# MOTOR.net
KiCad netlist of a schematic drawn in Altium Designer
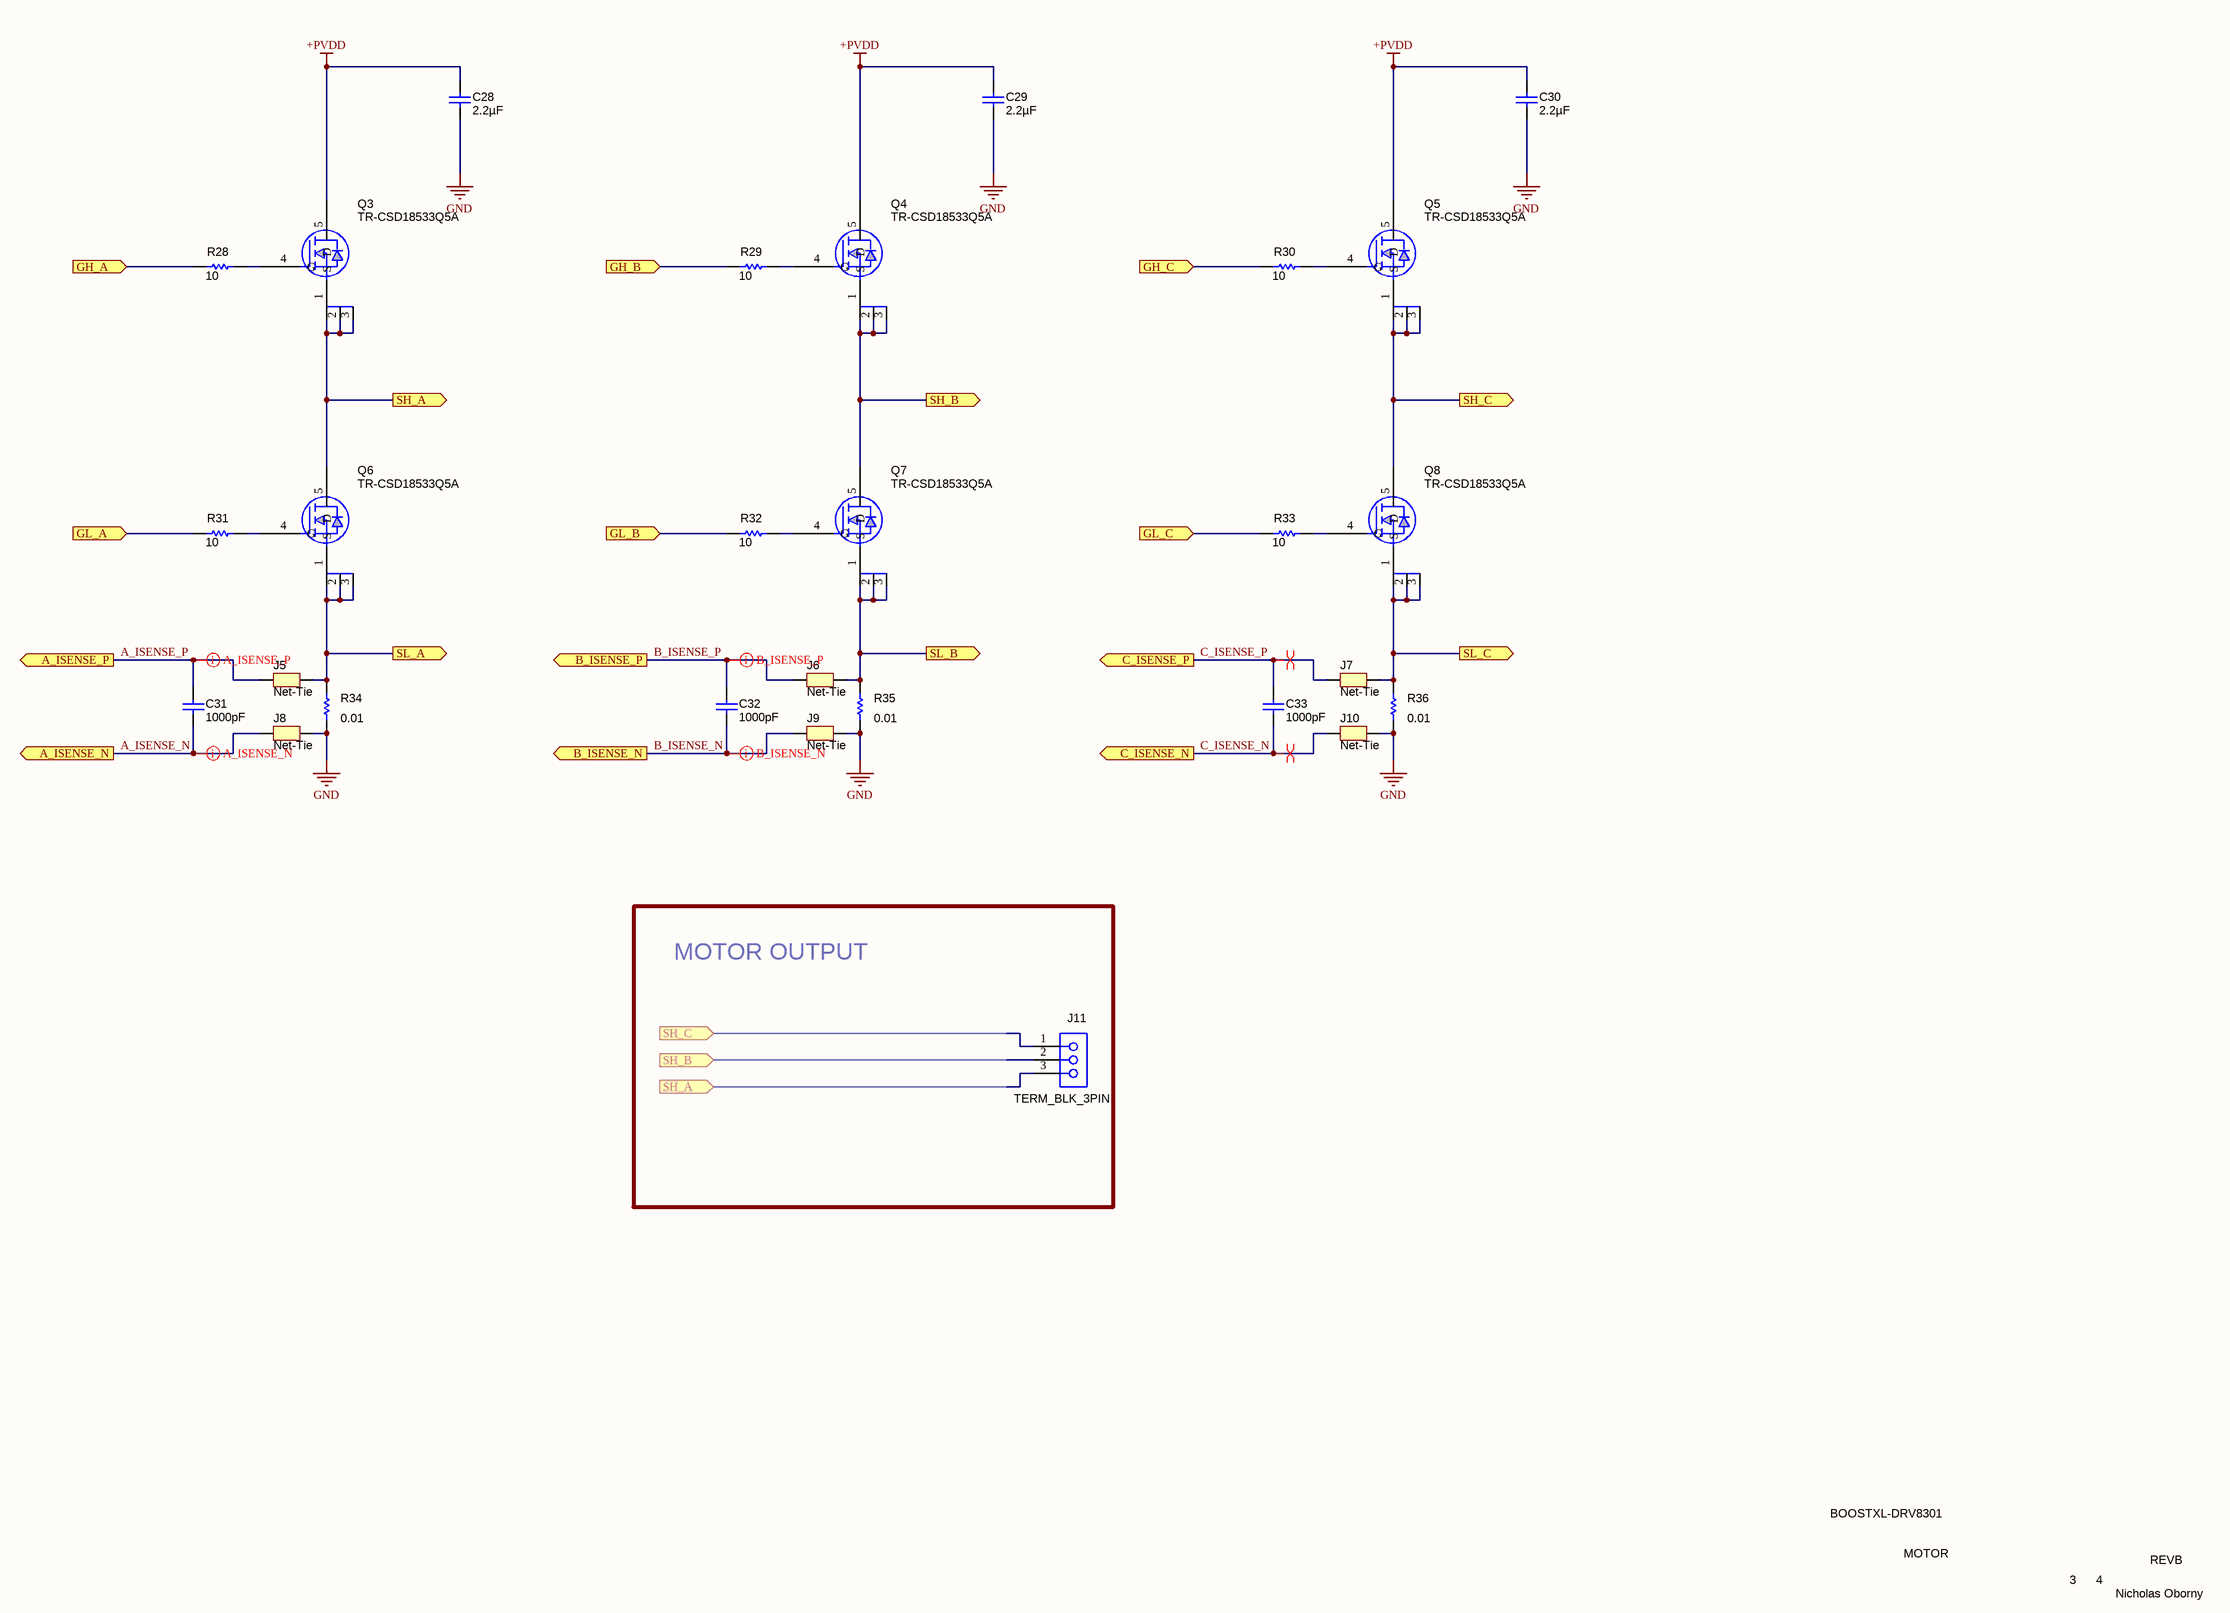
[diagram p0: MOTOR.SchDoc]

(export (version "E")
  (design (tool "Eeschema 10.0.6"))
  (components
    (comp (ref "C28")
      (value "GRM32ER72A225KA35L")
      (footprint "1210L")
      (description "CAP, CERM, 2.2uF, 100V, +/-10%, X7R, 1210")
      (fields
        (field (name "VALUEDISPLAYED") "2.2µF")
        (field (name "MANUFACTURER") "MuRata")
        (field (name "PUBLISHER") "Texas Instruments")
      )
      (libsource (lib "Capacitor_Ceramic") (part "GRM32ER72A225KA35L"))
    )
    (comp (ref "C29")
      (value "GRM32ER72A225KA35L")
      (footprint "1210L")
      (description "CAP, CERM, 2.2uF, 100V, +/-10%, X7R, 1210")
      (fields
        (field (name "VALUEDISPLAYED") "2.2µF")
        (field (name "MANUFACTURER") "MuRata")
        (field (name "PUBLISHER") "Texas Instruments")
      )
      (libsource (lib "Capacitor_Ceramic") (part "GRM32ER72A225KA35L"))
    )
    (comp (ref "C30")
      (value "GRM32ER72A225KA35L")
      (footprint "1210L")
      (description "CAP, CERM, 2.2uF, 100V, +/-10%, X7R, 1210")
      (fields
        (field (name "VALUEDISPLAYED") "2.2µF")
        (field (name "MANUFACTURER") "MuRata")
        (field (name "PUBLISHER") "Texas Instruments")
      )
      (libsource (lib "Capacitor_Ceramic") (part "GRM32ER72A225KA35L"))
    )
    (comp (ref "C31")
      (value "C0603C102J5GAC")
      (footprint "0603")
      (description "CAP, CERM, 1000pF, 50V, +/-5%, C0G/NP0, 0603")
      (fields
        (field (name "VALUEDISPLAYED") "1000pF")
        (field (name "MANUFACTURER") "Kemet")
        (field (name "PUBLISHER") "Texas Instruments")
      )
      (libsource (lib "Capacitor_Ceramic") (part "C0603C102J5GAC"))
    )
    (comp (ref "C32")
      (value "C0603C102J5GAC")
      (footprint "0603")
      (description "CAP, CERM, 1000pF, 50V, +/-5%, C0G/NP0, 0603")
      (fields
        (field (name "VALUEDISPLAYED") "1000pF")
        (field (name "MANUFACTURER") "Kemet")
        (field (name "PUBLISHER") "Texas Instruments")
      )
      (libsource (lib "Capacitor_Ceramic") (part "C0603C102J5GAC"))
    )
    (comp (ref "C33")
      (value "C0603C102J5GAC")
      (footprint "0603")
      (description "CAP, CERM, 1000pF, 50V, +/-5%, C0G/NP0, 0603")
      (fields
        (field (name "VALUEDISPLAYED") "1000pF")
        (field (name "MANUFACTURER") "Kemet")
        (field (name "PUBLISHER") "Texas Instruments")
      )
      (libsource (lib "Capacitor_Ceramic") (part "C0603C102J5GAC"))
    )
    (comp (ref "J5")
      (value "Net-Tie")
      (footprint "Net-Tie_10mil")
      (description "Single point connection between nets.")
      (fields (field (name "SYMBOLCREATOR") "codlsc") (field (name "PUBLISHER") "Texas Instruments"))
      (libsource (lib "MiscParts") (part "Net-Tie"))
    )
    (comp (ref "J6")
      (value "Net-Tie")
      (footprint "Net-Tie_10mil")
      (description "Single point connection between nets.")
      (fields (field (name "SYMBOLCREATOR") "codlsc") (field (name "PUBLISHER") "Texas Instruments"))
      (libsource (lib "MiscParts") (part "Net-Tie"))
    )
    (comp (ref "J7")
      (value "Net-Tie")
      (footprint "Net-Tie_10mil")
      (description "Single point connection between nets.")
      (fields (field (name "SYMBOLCREATOR") "codlsc") (field (name "PUBLISHER") "Texas Instruments"))
      (libsource (lib "MiscParts") (part "Net-Tie"))
    )
    (comp (ref "J8")
      (value "Net-Tie")
      (footprint "Net-Tie_10mil")
      (description "Single point connection between nets.")
      (fields (field (name "SYMBOLCREATOR") "codlsc") (field (name "PUBLISHER") "Texas Instruments"))
      (libsource (lib "MiscParts") (part "Net-Tie"))
    )
    (comp (ref "J9")
      (value "Net-Tie")
      (footprint "Net-Tie_10mil")
      (description "Single point connection between nets.")
      (fields (field (name "SYMBOLCREATOR") "codlsc") (field (name "PUBLISHER") "Texas Instruments"))
      (libsource (lib "MiscParts") (part "Net-Tie"))
    )
    (comp (ref "J10")
      (value "Net-Tie")
      (footprint "Net-Tie_10mil")
      (description "Single point connection between nets.")
      (fields (field (name "SYMBOLCREATOR") "codlsc") (field (name "PUBLISHER") "Texas Instruments"))
      (libsource (lib "MiscParts") (part "Net-Tie"))
    )
    (comp (ref "J11")
      (value "TERM_BLK_3PIN")
      (footprint "CONN_ED120_3DS")
      (description "TERMINAL BLOCK 5.08MM VERT 3POS")
      (fields
        (field (name "PARTNUMBER") "OSTTA034163")
        (field (name "MANUFACTURER") "On-Shore Technology")
        (field (name "SYMBOLCREATOR") "a0412235")
        (field (name "PUBLISHER") "Texas Instruments")
      )
      (libsource (lib "Connectors") (part "ED120/3DS"))
    )
    (comp (ref "Q3")
      (value "TR-CSD18533Q5A")
      (footprint "QFN5X6MM")
      (description "MOSFET, N-Chan, 60V, 18A, 6.1 mOhm")
      (fields (field (name "MANUFACTURER") "TI") (field (name "PARTNUMBER") "CSD18533Q5A"))
      (libsource (lib "PADSlegacy_Active") (part "TR-CSD18533Q5A"))
    )
    (comp (ref "Q4")
      (value "TR-CSD18533Q5A")
      (footprint "QFN5X6MM")
      (description "MOSFET, N-Chan, 60V, 18A, 6.1 mOhm")
      (fields (field (name "MANUFACTURER") "TI") (field (name "PARTNUMBER") "CSD18533Q5A"))
      (libsource (lib "PADSlegacy_Active") (part "TR-CSD18533Q5A"))
    )
    (comp (ref "Q5")
      (value "TR-CSD18533Q5A")
      (footprint "QFN5X6MM")
      (description "MOSFET, N-Chan, 60V, 18A, 6.1 mOhm")
      (fields (field (name "MANUFACTURER") "TI") (field (name "PARTNUMBER") "CSD18533Q5A"))
      (libsource (lib "PADSlegacy_Active") (part "TR-CSD18533Q5A"))
    )
    (comp (ref "Q6")
      (value "TR-CSD18533Q5A")
      (footprint "QFN5X6MM")
      (description "MOSFET, N-Chan, 60V, 18A, 6.1 mOhm")
      (fields (field (name "MANUFACTURER") "TI") (field (name "PARTNUMBER") "CSD18533Q5A"))
      (libsource (lib "PADSlegacy_Active") (part "TR-CSD18533Q5A"))
    )
    (comp (ref "Q7")
      (value "TR-CSD18533Q5A")
      (footprint "QFN5X6MM")
      (description "MOSFET, N-Chan, 60V, 18A, 6.1 mOhm")
      (fields (field (name "MANUFACTURER") "TI") (field (name "PARTNUMBER") "CSD18533Q5A"))
      (libsource (lib "PADSlegacy_Active") (part "TR-CSD18533Q5A"))
    )
    (comp (ref "Q8")
      (value "TR-CSD18533Q5A")
      (footprint "QFN5X6MM")
      (description "MOSFET, N-Chan, 60V, 18A, 6.1 mOhm")
      (fields (field (name "MANUFACTURER") "TI") (field (name "PARTNUMBER") "CSD18533Q5A"))
      (libsource (lib "PADSlegacy_Active") (part "TR-CSD18533Q5A"))
    )
    (comp (ref "R28")
      (value "10")
      (footprint "0603L")
      (description "RES, 10 ohm, 5%, 0.1W, 0603")
      (fields
        (field (name "PARTNUMBER") "CRCW060310R0JNEA")
        (field (name "MANUFACTURER") "Vishay-Dale")
        (field (name "PUBLISHER") "Texas Instruments")
      )
      (libsource (lib "Resistor_0603") (part "CRCW060310R0JNEA"))
    )
    (comp (ref "R29")
      (value "10")
      (footprint "0603L")
      (description "RES, 10 ohm, 5%, 0.1W, 0603")
      (fields
        (field (name "PARTNUMBER") "CRCW060310R0JNEA")
        (field (name "MANUFACTURER") "Vishay-Dale")
        (field (name "PUBLISHER") "Texas Instruments")
      )
      (libsource (lib "Resistor_0603") (part "CRCW060310R0JNEA"))
    )
    (comp (ref "R30")
      (value "10")
      (footprint "0603L")
      (description "RES, 10 ohm, 5%, 0.1W, 0603")
      (fields
        (field (name "PARTNUMBER") "CRCW060310R0JNEA")
        (field (name "MANUFACTURER") "Vishay-Dale")
        (field (name "PUBLISHER") "Texas Instruments")
      )
      (libsource (lib "Resistor_0603") (part "CRCW060310R0JNEA"))
    )
    (comp (ref "R31")
      (value "10")
      (footprint "0603L")
      (description "RES, 10 ohm, 5%, 0.1W, 0603")
      (fields
        (field (name "PARTNUMBER") "CRCW060310R0JNEA")
        (field (name "MANUFACTURER") "Vishay-Dale")
        (field (name "PUBLISHER") "Texas Instruments")
      )
      (libsource (lib "Resistor_0603") (part "CRCW060310R0JNEA"))
    )
    (comp (ref "R32")
      (value "10")
      (footprint "0603L")
      (description "RES, 10 ohm, 5%, 0.1W, 0603")
      (fields
        (field (name "PARTNUMBER") "CRCW060310R0JNEA")
        (field (name "MANUFACTURER") "Vishay-Dale")
        (field (name "PUBLISHER") "Texas Instruments")
      )
      (libsource (lib "Resistor_0603") (part "CRCW060310R0JNEA"))
    )
    (comp (ref "R33")
      (value "10")
      (footprint "0603L")
      (description "RES, 10 ohm, 5%, 0.1W, 0603")
      (fields
        (field (name "PARTNUMBER") "CRCW060310R0JNEA")
        (field (name "MANUFACTURER") "Vishay-Dale")
        (field (name "PUBLISHER") "Texas Instruments")
      )
      (libsource (lib "Resistor_0603") (part "CRCW060310R0JNEA"))
    )
    (comp (ref "R34")
      (value "0.01")
      (footprint "2512M")
      (description "RES, 0.01 ohm, 1%, 3W, 2512")
      (fields
        (field (name "PARTNUMBER") "CRA2512-FZ-R010ELF")
        (field (name "MANUFACTURER") "Bourns")
        (field (name "PUBLISHER") "Texas Instruments")
      )
      (libsource (lib "Resistor_OtherSMT") (part "CRA2512-FZ-R010ELF"))
    )
    (comp (ref "R35")
      (value "0.01")
      (footprint "2512M")
      (description "RES, 0.01 ohm, 1%, 3W, 2512")
      (fields
        (field (name "PARTNUMBER") "CRA2512-FZ-R010ELF")
        (field (name "MANUFACTURER") "Bourns")
        (field (name "PUBLISHER") "Texas Instruments")
      )
      (libsource (lib "Resistor_OtherSMT") (part "CRA2512-FZ-R010ELF"))
    )
    (comp (ref "R36")
      (value "0.01")
      (footprint "2512M")
      (description "RES, 0.01 ohm, 1%, 3W, 2512")
      (fields
        (field (name "PARTNUMBER") "CRA2512-FZ-R010ELF")
        (field (name "MANUFACTURER") "Bourns")
        (field (name "PUBLISHER") "Texas Instruments")
      )
      (libsource (lib "Resistor_OtherSMT") (part "CRA2512-FZ-R010ELF"))
    )
  )
  (nets
    (net (code "1") (name "+PVDD") (class "Default")
      (node (ref "C28") (pin "1") (pinfunction "1_1") (pintype "passive"))
      (node (ref "C29") (pin "1") (pinfunction "1_1") (pintype "passive"))
      (node (ref "C30") (pin "1") (pinfunction "1_1") (pintype "passive"))
      (node (ref "Q3") (pin "5") (pinfunction "D_5") (pintype "passive"))
      (node (ref "Q4") (pin "5") (pinfunction "D_5") (pintype "passive"))
      (node (ref "Q5") (pin "5") (pinfunction "D_5") (pintype "passive"))
    )
    (net (code "2") (name "/A_ISENSE_N") (class "Default")
      (node (ref "C31") (pin "2") (pinfunction "2_2") (pintype "passive"))
      (node (ref "J8") (pin "2") (pinfunction "2_2") (pintype "passive"))
    )
    (net (code "3") (name "/A_ISENSE_P") (class "Default")
      (node (ref "C31") (pin "1") (pinfunction "1_1") (pintype "passive"))
      (node (ref "J5") (pin "2") (pinfunction "2_2") (pintype "passive"))
    )
    (net (code "4") (name "/B_ISENSE_N") (class "Default")
      (node (ref "C32") (pin "2") (pinfunction "2_2") (pintype "passive"))
      (node (ref "J9") (pin "2") (pinfunction "2_2") (pintype "passive"))
    )
    (net (code "5") (name "/B_ISENSE_P") (class "Default")
      (node (ref "C32") (pin "1") (pinfunction "1_1") (pintype "passive"))
      (node (ref "J6") (pin "2") (pinfunction "2_2") (pintype "passive"))
    )
    (net (code "6") (name "/C_ISENSE_N") (class "Default")
      (node (ref "C33") (pin "2") (pinfunction "2_2") (pintype "passive"))
      (node (ref "J10") (pin "2") (pinfunction "2_2") (pintype "passive"))
    )
    (net (code "7") (name "/C_ISENSE_P") (class "Default")
      (node (ref "C33") (pin "1") (pinfunction "1_1") (pintype "passive"))
      (node (ref "J7") (pin "2") (pinfunction "2_2") (pintype "passive"))
    )
    (net (code "8") (name "/GH_A") (class "Default")
      (node (ref "R28") (pin "1") (pinfunction "1_1") (pintype "passive"))
    )
    (net (code "9") (name "/GH_B") (class "Default")
      (node (ref "R29") (pin "1") (pinfunction "1_1") (pintype "passive"))
    )
    (net (code "10") (name "/GH_C") (class "Default")
      (node (ref "R30") (pin "1") (pinfunction "1_1") (pintype "passive"))
    )
    (net (code "11") (name "/GL_A") (class "Default")
      (node (ref "R31") (pin "1") (pinfunction "1_1") (pintype "passive"))
    )
    (net (code "12") (name "/GL_B") (class "Default")
      (node (ref "R32") (pin "1") (pinfunction "1_1") (pintype "passive"))
    )
    (net (code "13") (name "/GL_C") (class "Default")
      (node (ref "R33") (pin "1") (pinfunction "1_1") (pintype "passive"))
    )
    (net (code "14") (name "/SH_A") (class "Default")
      (node (ref "J11") (pin "3") (pinfunction "3_3") (pintype "passive"))
      (node (ref "Q3") (pin "1") (pinfunction "S_1") (pintype "passive"))
      (node (ref "Q3") (pin "2") (pintype "passive"))
      (node (ref "Q3") (pin "3") (pintype "passive"))
      (node (ref "Q6") (pin "5") (pinfunction "D_5") (pintype "passive"))
    )
    (net (code "15") (name "/SH_B") (class "Default")
      (node (ref "J11") (pin "2") (pinfunction "2_2") (pintype "passive"))
      (node (ref "Q4") (pin "1") (pinfunction "S_1") (pintype "passive"))
      (node (ref "Q4") (pin "2") (pintype "passive"))
      (node (ref "Q4") (pin "3") (pintype "passive"))
      (node (ref "Q7") (pin "5") (pinfunction "D_5") (pintype "passive"))
    )
    (net (code "16") (name "/SH_C") (class "Default")
      (node (ref "J11") (pin "1") (pinfunction "1_1") (pintype "passive"))
      (node (ref "Q5") (pin "1") (pinfunction "S_1") (pintype "passive"))
      (node (ref "Q5") (pin "2") (pintype "passive"))
      (node (ref "Q5") (pin "3") (pintype "passive"))
      (node (ref "Q8") (pin "5") (pinfunction "D_5") (pintype "passive"))
    )
    (net (code "17") (name "/SL_A") (class "Default")
      (node (ref "J5") (pin "1") (pinfunction "1_1") (pintype "passive"))
      (node (ref "Q6") (pin "1") (pinfunction "S_1") (pintype "passive"))
      (node (ref "Q6") (pin "2") (pintype "passive"))
      (node (ref "Q6") (pin "3") (pintype "passive"))
      (node (ref "R34") (pin "2") (pinfunction "2_2") (pintype "passive"))
    )
    (net (code "18") (name "/SL_B") (class "Default")
      (node (ref "J6") (pin "1") (pinfunction "1_1") (pintype "passive"))
      (node (ref "Q7") (pin "1") (pinfunction "S_1") (pintype "passive"))
      (node (ref "Q7") (pin "2") (pintype "passive"))
      (node (ref "Q7") (pin "3") (pintype "passive"))
      (node (ref "R35") (pin "2") (pinfunction "2_2") (pintype "passive"))
    )
    (net (code "19") (name "/SL_C") (class "Default")
      (node (ref "J7") (pin "1") (pinfunction "1_1") (pintype "passive"))
      (node (ref "Q8") (pin "1") (pinfunction "S_1") (pintype "passive"))
      (node (ref "Q8") (pin "2") (pintype "passive"))
      (node (ref "Q8") (pin "3") (pintype "passive"))
      (node (ref "R36") (pin "2") (pinfunction "2_2") (pintype "passive"))
    )
    (net (code "20") (name "GND") (class "Default")
      (node (ref "C28") (pin "2") (pinfunction "2_2") (pintype "passive"))
      (node (ref "C29") (pin "2") (pinfunction "2_2") (pintype "passive"))
      (node (ref "C30") (pin "2") (pinfunction "2_2") (pintype "passive"))
      (node (ref "J10") (pin "1") (pinfunction "1_1") (pintype "passive"))
      (node (ref "J8") (pin "1") (pinfunction "1_1") (pintype "passive"))
      (node (ref "J9") (pin "1") (pinfunction "1_1") (pintype "passive"))
      (node (ref "R34") (pin "1") (pinfunction "1_1") (pintype "passive"))
      (node (ref "R35") (pin "1") (pinfunction "1_1") (pintype "passive"))
      (node (ref "R36") (pin "1") (pinfunction "1_1") (pintype "passive"))
    )
    (net (code "21") (name "Net-(Q3-G)") (class "Default")
      (node (ref "Q3") (pin "4") (pinfunction "G_4") (pintype "passive"))
      (node (ref "R28") (pin "2") (pinfunction "2_2") (pintype "passive"))
    )
    (net (code "22") (name "Net-(Q4-G)") (class "Default")
      (node (ref "Q4") (pin "4") (pinfunction "G_4") (pintype "passive"))
      (node (ref "R29") (pin "2") (pinfunction "2_2") (pintype "passive"))
    )
    (net (code "23") (name "Net-(Q5-G)") (class "Default")
      (node (ref "Q5") (pin "4") (pinfunction "G_4") (pintype "passive"))
      (node (ref "R30") (pin "2") (pinfunction "2_2") (pintype "passive"))
    )
    (net (code "24") (name "Net-(Q6-G)") (class "Default")
      (node (ref "Q6") (pin "4") (pinfunction "G_4") (pintype "passive"))
      (node (ref "R31") (pin "2") (pinfunction "2_2") (pintype "passive"))
    )
    (net (code "25") (name "Net-(Q7-G)") (class "Default")
      (node (ref "Q7") (pin "4") (pinfunction "G_4") (pintype "passive"))
      (node (ref "R32") (pin "2") (pinfunction "2_2") (pintype "passive"))
    )
    (net (code "26") (name "Net-(Q8-G)") (class "Default")
      (node (ref "Q8") (pin "4") (pinfunction "G_4") (pintype "passive"))
      (node (ref "R33") (pin "2") (pinfunction "2_2") (pintype "passive"))
    )
  )
)
